# PowerTXBoard.net
KiCad netlist of a schematic drawn in EAGLE
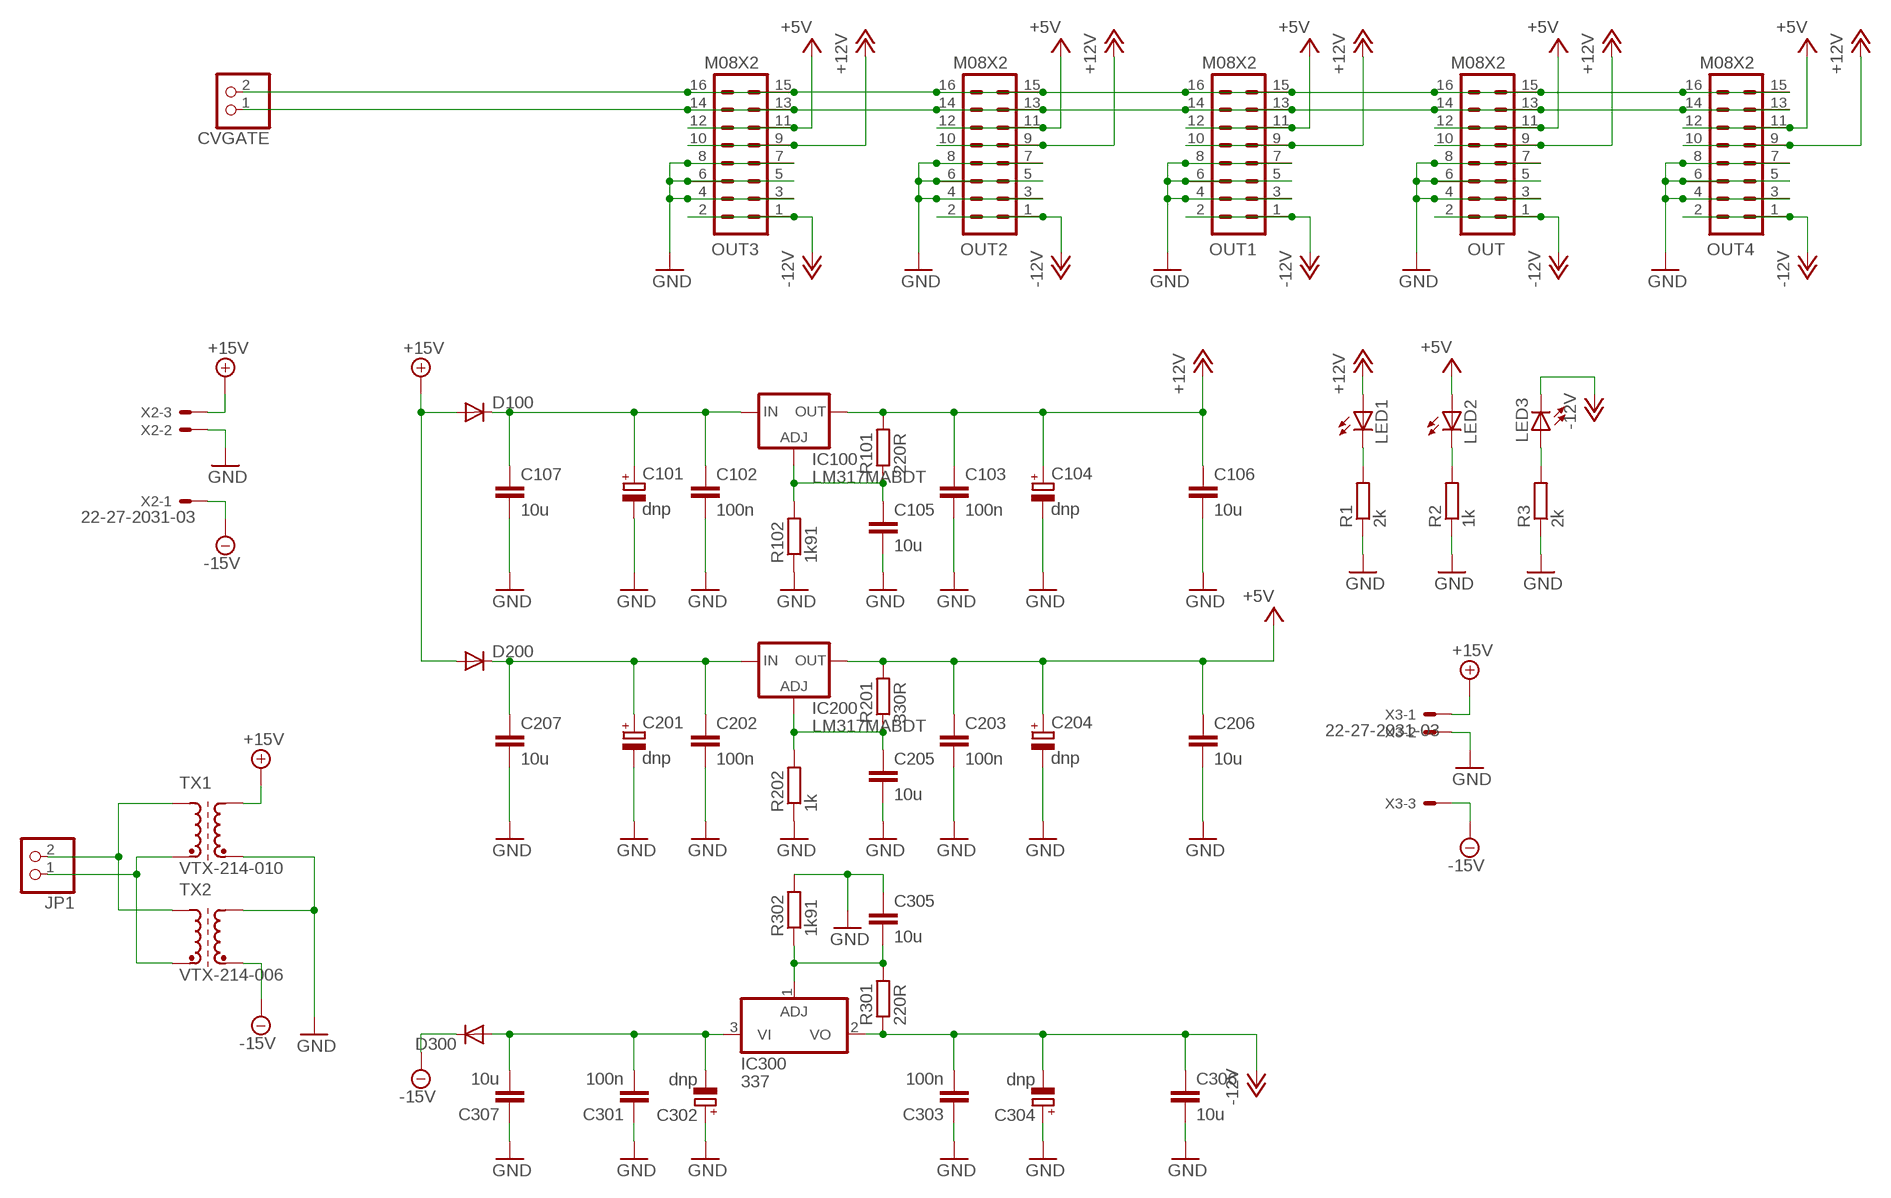
[diagram p0: schematic, sheet 1]

(export (version "E")
  (design (tool "Eeschema 10.0.6"))
  (components
    (comp (ref "C101")
      (value "dnp")
      (footprint "eagle-import:CPOL-5")
      (libsource (lib "eagle-import") (part "CPOL-EU153CLV-0505"))
    )
    (comp (ref "C102")
      (value "100n")
      (footprint "eagle-import:C0603")
      (libsource (lib "eagle-import") (part "C-EUC0603"))
    )
    (comp (ref "C103")
      (value "100n")
      (footprint "eagle-import:C0603")
      (libsource (lib "eagle-import") (part "C-EUC0603"))
    )
    (comp (ref "C104")
      (value "dnp")
      (footprint "eagle-import:CPOL-5")
      (libsource (lib "eagle-import") (part "CPOL-EU153CLV-0505"))
    )
    (comp (ref "C105")
      (value "10u")
      (footprint "eagle-import:C1206")
      (libsource (lib "eagle-import") (part "C-EUC1206"))
    )
    (comp (ref "C106")
      (value "10u")
      (footprint "eagle-import:C1206")
      (libsource (lib "eagle-import") (part "C-EUC1206"))
    )
    (comp (ref "C107")
      (value "10u")
      (footprint "eagle-import:C1206")
      (libsource (lib "eagle-import") (part "C-EUC1206"))
    )
    (comp (ref "C201")
      (value "dnp")
      (footprint "eagle-import:CPOL-5")
      (libsource (lib "eagle-import") (part "CPOL-EU153CLV-0505"))
    )
    (comp (ref "C202")
      (value "100n")
      (footprint "eagle-import:C0603")
      (libsource (lib "eagle-import") (part "C-EUC0603"))
    )
    (comp (ref "C203")
      (value "100n")
      (footprint "eagle-import:C0603")
      (libsource (lib "eagle-import") (part "C-EUC0603"))
    )
    (comp (ref "C204")
      (value "dnp")
      (footprint "eagle-import:CPOL-5")
      (libsource (lib "eagle-import") (part "CPOL-EU153CLV-0505"))
    )
    (comp (ref "C205")
      (value "10u")
      (footprint "eagle-import:C1206")
      (libsource (lib "eagle-import") (part "C-EUC1206"))
    )
    (comp (ref "C206")
      (value "10u")
      (footprint "eagle-import:C1206")
      (libsource (lib "eagle-import") (part "C-EUC1206"))
    )
    (comp (ref "C207")
      (value "10u")
      (footprint "eagle-import:C1206")
      (libsource (lib "eagle-import") (part "C-EUC1206"))
    )
    (comp (ref "C301")
      (value "100n")
      (footprint "eagle-import:C0603")
      (libsource (lib "eagle-import") (part "C-EUC0603"))
    )
    (comp (ref "C302")
      (value "dnp")
      (footprint "eagle-import:CPOL-5")
      (libsource (lib "eagle-import") (part "CPOL-EU153CLV-0505"))
    )
    (comp (ref "C303")
      (value "100n")
      (footprint "eagle-import:C0603")
      (libsource (lib "eagle-import") (part "C-EUC0603"))
    )
    (comp (ref "C304")
      (value "dnp")
      (footprint "eagle-import:CPOL-5")
      (libsource (lib "eagle-import") (part "CPOL-EU153CLV-0505"))
    )
    (comp (ref "C305")
      (value "10u")
      (footprint "eagle-import:C1206")
      (libsource (lib "eagle-import") (part "C-EUC1206"))
    )
    (comp (ref "C306")
      (value "10u")
      (footprint "eagle-import:C1206")
      (libsource (lib "eagle-import") (part "C-EUC1206"))
    )
    (comp (ref "C307")
      (value "10u")
      (footprint "eagle-import:C1206")
      (libsource (lib "eagle-import") (part "C-EUC1206"))
    )
    (comp (ref "CVGATE")
      (value "PINHD-1X2")
      (footprint "eagle-import:1X02")
      (libsource (lib "eagle-import") (part "PINHD-1X2"))
    )
    (comp (ref "D100")
      (value "DIODESMA")
      (footprint "eagle-import:SMA-DIODE")
      (libsource (lib "eagle-import") (part "DIODESMA"))
    )
    (comp (ref "D200")
      (value "DIODESMA")
      (footprint "eagle-import:SMA-DIODE")
      (libsource (lib "eagle-import") (part "DIODESMA"))
    )
    (comp (ref "D300")
      (value "DIODESMA")
      (footprint "eagle-import:SMA-DIODE")
      (libsource (lib "eagle-import") (part "DIODESMA"))
    )
    (comp (ref "IC100")
      (value "LM317MABDT")
      (footprint "eagle-import:DPACK")
      (libsource (lib "eagle-import") (part "v-reg_LM317?MABDT"))
    )
    (comp (ref "IC200")
      (value "LM317MABDT")
      (footprint "eagle-import:DPACK")
      (libsource (lib "eagle-import") (part "v-reg_LM317?MABDT"))
    )
    (comp (ref "IC300")
      (value "337")
      (footprint "eagle-import:TO252")
      (libsource (lib "eagle-import") (part "337"))
    )
    (comp (ref "JP1")
      (value "PINHD-1X2")
      (footprint "eagle-import:1X02")
      (libsource (lib "eagle-import") (part "PINHD-1X2"))
    )
    (comp (ref "LED1")
      (value "LEDCHIPLED_1206")
      (footprint "eagle-import:CHIPLED_1206")
      (libsource (lib "eagle-import") (part "LEDCHIPLED_1206"))
    )
    (comp (ref "LED2")
      (value "LEDCHIPLED_1206")
      (footprint "eagle-import:CHIPLED_1206")
      (libsource (lib "eagle-import") (part "LEDCHIPLED_1206"))
    )
    (comp (ref "LED3")
      (value "LEDCHIPLED_1206")
      (footprint "eagle-import:CHIPLED_1206")
      (libsource (lib "eagle-import") (part "LEDCHIPLED_1206"))
    )
    (comp (ref "OUT")
      (value "M08X2")
      (footprint "eagle-import:2X8")
      (libsource (lib "eagle-import") (part "M08X2"))
    )
    (comp (ref "OUT1")
      (value "M08X2")
      (footprint "eagle-import:2X8")
      (libsource (lib "eagle-import") (part "M08X2"))
    )
    (comp (ref "OUT2")
      (value "M08X2")
      (footprint "eagle-import:2X8")
      (libsource (lib "eagle-import") (part "M08X2"))
    )
    (comp (ref "OUT3")
      (value "M08X2")
      (footprint "eagle-import:2X8")
      (libsource (lib "eagle-import") (part "M08X2"))
    )
    (comp (ref "OUT4")
      (value "M08X2")
      (footprint "eagle-import:2X8")
      (libsource (lib "eagle-import") (part "M08X2"))
    )
    (comp (ref "R1")
      (value "2k")
      (footprint "eagle-import:0603")
      (libsource (lib "eagle-import") (part "R-EU_0603"))
    )
    (comp (ref "R2")
      (value "1k")
      (footprint "eagle-import:0603")
      (libsource (lib "eagle-import") (part "R-EU_0603"))
    )
    (comp (ref "R3")
      (value "2k")
      (footprint "eagle-import:0603")
      (libsource (lib "eagle-import") (part "R-EU_0603"))
    )
    (comp (ref "R101")
      (value "220R")
      (footprint "eagle-import:0603")
      (libsource (lib "eagle-import") (part "R-EU_0603"))
    )
    (comp (ref "R102")
      (value "1k91")
      (footprint "eagle-import:0603")
      (libsource (lib "eagle-import") (part "R-EU_0603"))
    )
    (comp (ref "R201")
      (value "330R")
      (footprint "eagle-import:0603")
      (libsource (lib "eagle-import") (part "R-EU_0603"))
    )
    (comp (ref "R202")
      (value "1k")
      (footprint "eagle-import:0603")
      (libsource (lib "eagle-import") (part "R-EU_0603"))
    )
    (comp (ref "R301")
      (value "220R")
      (footprint "eagle-import:0603")
      (libsource (lib "eagle-import") (part "R-EU_0603"))
    )
    (comp (ref "R302")
      (value "1k91")
      (footprint "eagle-import:0603")
      (libsource (lib "eagle-import") (part "R-EU_0603"))
    )
    (comp (ref "TX1")
      (value "VTX-214-010")
      (footprint "eagle-import:VTX-214-006")
      (libsource (lib "eagle-import") (part "VTX-214-006"))
    )
    (comp (ref "TX2")
      (value "VTX-214-006")
      (footprint "eagle-import:VTX-214-006")
      (libsource (lib "eagle-import") (part "VTX-214-006"))
    )
    (comp (ref "X2")
      (value "22-27-2031-03")
      (footprint "eagle-import:6410-03")
      (libsource (lib "eagle-import") (part "22-?-0327-2031"))
    )
    (comp (ref "X3")
      (value "22-27-2031-03")
      (footprint "eagle-import:6410-03")
      (libsource (lib "eagle-import") (part "22-?-0327-2031"))
    )
  )
  (nets
    (net (code "1") (name "+5V") (class "Default")
      (node (ref "C203") (pin "1") (pinfunction "1_1") (pintype "passive"))
      (node (ref "C204") (pin "+") (pinfunction "+_+") (pintype "passive"))
      (node (ref "C206") (pin "1") (pinfunction "1_1") (pintype "passive"))
      (node (ref "IC200") (pin "4") (pinfunction "OUT_4") (pintype "passive"))
      (node (ref "LED2") (pin "A") (pinfunction "A_A") (pintype "passive"))
      (node (ref "OUT") (pin "11") (pinfunction "11_11") (pintype "passive"))
      (node (ref "OUT") (pin "12") (pinfunction "12_12") (pintype "passive"))
      (node (ref "OUT1") (pin "11") (pinfunction "11_11") (pintype "passive"))
      (node (ref "OUT1") (pin "12") (pinfunction "12_12") (pintype "passive"))
      (node (ref "OUT2") (pin "11") (pinfunction "11_11") (pintype "passive"))
      (node (ref "OUT2") (pin "12") (pinfunction "12_12") (pintype "passive"))
      (node (ref "OUT3") (pin "11") (pinfunction "11_11") (pintype "passive"))
      (node (ref "OUT3") (pin "12") (pinfunction "12_12") (pintype "passive"))
      (node (ref "OUT4") (pin "11") (pinfunction "11_11") (pintype "passive"))
      (node (ref "OUT4") (pin "12") (pinfunction "12_12") (pintype "passive"))
      (node (ref "R201") (pin "2") (pinfunction "2_2") (pintype "passive"))
    )
    (net (code "2") (name "+12V") (class "Default")
      (node (ref "C103") (pin "1") (pinfunction "1_1") (pintype "passive"))
      (node (ref "C104") (pin "+") (pinfunction "+_+") (pintype "passive"))
      (node (ref "C106") (pin "1") (pinfunction "1_1") (pintype "passive"))
      (node (ref "IC100") (pin "4") (pinfunction "OUT_4") (pintype "passive"))
      (node (ref "LED1") (pin "A") (pinfunction "A_A") (pintype "passive"))
      (node (ref "OUT") (pin "10") (pinfunction "10_10") (pintype "passive"))
      (node (ref "OUT") (pin "9") (pinfunction "9_9") (pintype "passive"))
      (node (ref "OUT1") (pin "10") (pinfunction "10_10") (pintype "passive"))
      (node (ref "OUT1") (pin "9") (pinfunction "9_9") (pintype "passive"))
      (node (ref "OUT2") (pin "10") (pinfunction "10_10") (pintype "passive"))
      (node (ref "OUT2") (pin "9") (pinfunction "9_9") (pintype "passive"))
      (node (ref "OUT3") (pin "10") (pinfunction "10_10") (pintype "passive"))
      (node (ref "OUT3") (pin "9") (pinfunction "9_9") (pintype "passive"))
      (node (ref "OUT4") (pin "10") (pinfunction "10_10") (pintype "passive"))
      (node (ref "OUT4") (pin "9") (pinfunction "9_9") (pintype "passive"))
      (node (ref "R101") (pin "2") (pinfunction "2_2") (pintype "passive"))
    )
    (net (code "3") (name "+15V") (class "Default")
      (node (ref "D100") (pin "A") (pinfunction "A_A") (pintype "passive"))
      (node (ref "D200") (pin "A") (pinfunction "A_A") (pintype "passive"))
      (node (ref "TX1") (pin "P$3") (pinfunction "A2_P$3") (pintype "passive"))
      (node (ref "X2") (pin "3") (pinfunction "S_3") (pintype "passive"))
      (node (ref "X3") (pin "1") (pinfunction "S_1") (pintype "passive"))
    )
    (net (code "4") (name "-12V") (class "Default")
      (node (ref "C303") (pin "2") (pinfunction "2_2") (pintype "passive"))
      (node (ref "C304") (pin "-") (pinfunction "-_-") (pintype "passive"))
      (node (ref "C306") (pin "1") (pinfunction "1_1") (pintype "passive"))
      (node (ref "IC300") (pin "2") (pinfunction "VO_2") (pintype "passive"))
      (node (ref "LED3") (pin "C") (pinfunction "C_C") (pintype "passive"))
      (node (ref "OUT") (pin "1") (pinfunction "1_1") (pintype "passive"))
      (node (ref "OUT") (pin "2") (pinfunction "2_2") (pintype "passive"))
      (node (ref "OUT1") (pin "1") (pinfunction "1_1") (pintype "passive"))
      (node (ref "OUT1") (pin "2") (pinfunction "2_2") (pintype "passive"))
      (node (ref "OUT2") (pin "1") (pinfunction "1_1") (pintype "passive"))
      (node (ref "OUT2") (pin "2") (pinfunction "2_2") (pintype "passive"))
      (node (ref "OUT3") (pin "1") (pinfunction "1_1") (pintype "passive"))
      (node (ref "OUT3") (pin "2") (pinfunction "2_2") (pintype "passive"))
      (node (ref "OUT4") (pin "1") (pinfunction "1_1") (pintype "passive"))
      (node (ref "OUT4") (pin "2") (pinfunction "2_2") (pintype "passive"))
      (node (ref "R301") (pin "1") (pinfunction "1_1") (pintype "passive"))
    )
    (net (code "5") (name "-15V") (class "Default")
      (node (ref "D300") (pin "C") (pinfunction "C_C") (pintype "passive"))
      (node (ref "TX2") (pin "P$4") (pinfunction "E2_P$4") (pintype "passive"))
      (node (ref "X2") (pin "1") (pinfunction "S_1") (pintype "passive"))
      (node (ref "X3") (pin "3") (pinfunction "S_3") (pintype "passive"))
    )
    (net (code "6") (name "GND") (class "Default")
      (node (ref "C101") (pin "-") (pinfunction "-_-") (pintype "passive"))
      (node (ref "C102") (pin "2") (pinfunction "2_2") (pintype "passive"))
      (node (ref "C103") (pin "2") (pinfunction "2_2") (pintype "passive"))
      (node (ref "C104") (pin "-") (pinfunction "-_-") (pintype "passive"))
      (node (ref "C105") (pin "2") (pinfunction "2_2") (pintype "passive"))
      (node (ref "C106") (pin "2") (pinfunction "2_2") (pintype "passive"))
      (node (ref "C107") (pin "2") (pinfunction "2_2") (pintype "passive"))
      (node (ref "C201") (pin "-") (pinfunction "-_-") (pintype "passive"))
      (node (ref "C202") (pin "2") (pinfunction "2_2") (pintype "passive"))
      (node (ref "C203") (pin "2") (pinfunction "2_2") (pintype "passive"))
      (node (ref "C204") (pin "-") (pinfunction "-_-") (pintype "passive"))
      (node (ref "C205") (pin "2") (pinfunction "2_2") (pintype "passive"))
      (node (ref "C206") (pin "2") (pinfunction "2_2") (pintype "passive"))
      (node (ref "C207") (pin "2") (pinfunction "2_2") (pintype "passive"))
      (node (ref "C301") (pin "1") (pinfunction "1_1") (pintype "passive"))
      (node (ref "C302") (pin "+") (pinfunction "+_+") (pintype "passive"))
      (node (ref "C303") (pin "1") (pinfunction "1_1") (pintype "passive"))
      (node (ref "C304") (pin "+") (pinfunction "+_+") (pintype "passive"))
      (node (ref "C305") (pin "1") (pinfunction "1_1") (pintype "passive"))
      (node (ref "C306") (pin "2") (pinfunction "2_2") (pintype "passive"))
      (node (ref "C307") (pin "1") (pinfunction "1_1") (pintype "passive"))
      (node (ref "OUT") (pin "3") (pinfunction "3_3") (pintype "passive"))
      (node (ref "OUT") (pin "4") (pinfunction "4_4") (pintype "passive"))
      (node (ref "OUT") (pin "5") (pinfunction "5_5") (pintype "passive"))
      (node (ref "OUT") (pin "6") (pinfunction "6_6") (pintype "passive"))
      (node (ref "OUT") (pin "7") (pinfunction "7_7") (pintype "passive"))
      (node (ref "OUT") (pin "8") (pinfunction "8_8") (pintype "passive"))
      (node (ref "OUT1") (pin "3") (pinfunction "3_3") (pintype "passive"))
      (node (ref "OUT1") (pin "4") (pinfunction "4_4") (pintype "passive"))
      (node (ref "OUT1") (pin "5") (pinfunction "5_5") (pintype "passive"))
      (node (ref "OUT1") (pin "6") (pinfunction "6_6") (pintype "passive"))
      (node (ref "OUT1") (pin "7") (pinfunction "7_7") (pintype "passive"))
      (node (ref "OUT1") (pin "8") (pinfunction "8_8") (pintype "passive"))
      (node (ref "OUT2") (pin "3") (pinfunction "3_3") (pintype "passive"))
      (node (ref "OUT2") (pin "4") (pinfunction "4_4") (pintype "passive"))
      (node (ref "OUT2") (pin "5") (pinfunction "5_5") (pintype "passive"))
      (node (ref "OUT2") (pin "6") (pinfunction "6_6") (pintype "passive"))
      (node (ref "OUT2") (pin "7") (pinfunction "7_7") (pintype "passive"))
      (node (ref "OUT2") (pin "8") (pinfunction "8_8") (pintype "passive"))
      (node (ref "OUT3") (pin "3") (pinfunction "3_3") (pintype "passive"))
      (node (ref "OUT3") (pin "4") (pinfunction "4_4") (pintype "passive"))
      (node (ref "OUT3") (pin "5") (pinfunction "5_5") (pintype "passive"))
      (node (ref "OUT3") (pin "6") (pinfunction "6_6") (pintype "passive"))
      (node (ref "OUT3") (pin "7") (pinfunction "7_7") (pintype "passive"))
      (node (ref "OUT3") (pin "8") (pinfunction "8_8") (pintype "passive"))
      (node (ref "OUT4") (pin "3") (pinfunction "3_3") (pintype "passive"))
      (node (ref "OUT4") (pin "4") (pinfunction "4_4") (pintype "passive"))
      (node (ref "OUT4") (pin "5") (pinfunction "5_5") (pintype "passive"))
      (node (ref "OUT4") (pin "6") (pinfunction "6_6") (pintype "passive"))
      (node (ref "OUT4") (pin "7") (pinfunction "7_7") (pintype "passive"))
      (node (ref "OUT4") (pin "8") (pinfunction "8_8") (pintype "passive"))
      (node (ref "R1") (pin "1") (pinfunction "1_1") (pintype "passive"))
      (node (ref "R102") (pin "1") (pinfunction "1_1") (pintype "passive"))
      (node (ref "R2") (pin "1") (pinfunction "1_1") (pintype "passive"))
      (node (ref "R202") (pin "1") (pinfunction "1_1") (pintype "passive"))
      (node (ref "R3") (pin "1") (pinfunction "1_1") (pintype "passive"))
      (node (ref "R302") (pin "2") (pinfunction "2_2") (pintype "passive"))
      (node (ref "TX1") (pin "P$4") (pinfunction "E2_P$4") (pintype "passive"))
      (node (ref "TX2") (pin "P$3") (pinfunction "A2_P$3") (pintype "passive"))
      (node (ref "X2") (pin "2") (pinfunction "S_2") (pintype "passive"))
      (node (ref "X3") (pin "2") (pinfunction "S_2") (pintype "passive"))
    )
    (net (code "7") (name "Net-(CVGATE-Pad1)") (class "Default")
      (node (ref "CVGATE") (pin "1") (pinfunction "1_1") (pintype "passive"))
      (node (ref "OUT") (pin "13") (pinfunction "13_13") (pintype "passive"))
      (node (ref "OUT") (pin "14") (pinfunction "14_14") (pintype "passive"))
      (node (ref "OUT1") (pin "13") (pinfunction "13_13") (pintype "passive"))
      (node (ref "OUT1") (pin "14") (pinfunction "14_14") (pintype "passive"))
      (node (ref "OUT2") (pin "13") (pinfunction "13_13") (pintype "passive"))
      (node (ref "OUT2") (pin "14") (pinfunction "14_14") (pintype "passive"))
      (node (ref "OUT3") (pin "13") (pinfunction "13_13") (pintype "passive"))
      (node (ref "OUT3") (pin "14") (pinfunction "14_14") (pintype "passive"))
      (node (ref "OUT4") (pin "13") (pinfunction "13_13") (pintype "passive"))
      (node (ref "OUT4") (pin "14") (pinfunction "14_14") (pintype "passive"))
    )
    (net (code "8") (name "Net-(CVGATE-Pad2)") (class "Default")
      (node (ref "CVGATE") (pin "2") (pinfunction "2_2") (pintype "passive"))
      (node (ref "OUT") (pin "15") (pinfunction "15_15") (pintype "passive"))
      (node (ref "OUT") (pin "16") (pinfunction "16_16") (pintype "passive"))
      (node (ref "OUT1") (pin "15") (pinfunction "15_15") (pintype "passive"))
      (node (ref "OUT1") (pin "16") (pinfunction "16_16") (pintype "passive"))
      (node (ref "OUT2") (pin "15") (pinfunction "15_15") (pintype "passive"))
      (node (ref "OUT2") (pin "16") (pinfunction "16_16") (pintype "passive"))
      (node (ref "OUT3") (pin "15") (pinfunction "15_15") (pintype "passive"))
      (node (ref "OUT3") (pin "16") (pinfunction "16_16") (pintype "passive"))
      (node (ref "OUT4") (pin "15") (pinfunction "15_15") (pintype "passive"))
      (node (ref "OUT4") (pin "16") (pinfunction "16_16") (pintype "passive"))
    )
    (net (code "9") (name "Net-(IC100-ADJ)") (class "Default")
      (node (ref "C105") (pin "1") (pinfunction "1_1") (pintype "passive"))
      (node (ref "IC100") (pin "1") (pinfunction "ADJ_1") (pintype "input"))
      (node (ref "R101") (pin "1") (pinfunction "1_1") (pintype "passive"))
      (node (ref "R102") (pin "2") (pinfunction "2_2") (pintype "passive"))
    )
    (net (code "10") (name "Net-(IC100-IN)") (class "Default")
      (node (ref "C101") (pin "+") (pinfunction "+_+") (pintype "passive"))
      (node (ref "C102") (pin "1") (pinfunction "1_1") (pintype "passive"))
      (node (ref "C107") (pin "1") (pinfunction "1_1") (pintype "passive"))
      (node (ref "D100") (pin "C") (pinfunction "C_C") (pintype "passive"))
      (node (ref "IC100") (pin "3") (pinfunction "IN_3") (pintype "input"))
    )
    (net (code "11") (name "Net-(IC200-ADJ)") (class "Default")
      (node (ref "C205") (pin "1") (pinfunction "1_1") (pintype "passive"))
      (node (ref "IC200") (pin "1") (pinfunction "ADJ_1") (pintype "input"))
      (node (ref "R201") (pin "1") (pinfunction "1_1") (pintype "passive"))
      (node (ref "R202") (pin "2") (pinfunction "2_2") (pintype "passive"))
    )
    (net (code "12") (name "Net-(IC200-IN)") (class "Default")
      (node (ref "C201") (pin "+") (pinfunction "+_+") (pintype "passive"))
      (node (ref "C202") (pin "1") (pinfunction "1_1") (pintype "passive"))
      (node (ref "C207") (pin "1") (pinfunction "1_1") (pintype "passive"))
      (node (ref "D200") (pin "C") (pinfunction "C_C") (pintype "passive"))
      (node (ref "IC200") (pin "3") (pinfunction "IN_3") (pintype "input"))
    )
    (net (code "13") (name "Net-(IC300-ADJ)") (class "Default")
      (node (ref "C305") (pin "2") (pinfunction "2_2") (pintype "passive"))
      (node (ref "IC300") (pin "1") (pinfunction "ADJ_1") (pintype "input"))
      (node (ref "R301") (pin "2") (pinfunction "2_2") (pintype "passive"))
      (node (ref "R302") (pin "1") (pinfunction "1_1") (pintype "passive"))
    )
    (net (code "14") (name "Net-(IC300-VI)") (class "Default")
      (node (ref "C301") (pin "2") (pinfunction "2_2") (pintype "passive"))
      (node (ref "C302") (pin "-") (pinfunction "-_-") (pintype "passive"))
      (node (ref "C307") (pin "2") (pinfunction "2_2") (pintype "passive"))
      (node (ref "D300") (pin "A") (pinfunction "A_A") (pintype "passive"))
      (node (ref "IC300") (pin "3") (pinfunction "VI_3") (pintype "input"))
    )
    (net (code "15") (name "Net-(LED1-PadC)") (class "Default")
      (node (ref "LED1") (pin "C") (pinfunction "C_C") (pintype "passive"))
      (node (ref "R1") (pin "2") (pinfunction "2_2") (pintype "passive"))
    )
    (net (code "16") (name "Net-(LED2-PadC)") (class "Default")
      (node (ref "LED2") (pin "C") (pinfunction "C_C") (pintype "passive"))
      (node (ref "R2") (pin "2") (pinfunction "2_2") (pintype "passive"))
    )
    (net (code "17") (name "Net-(LED3-PadA)") (class "Default")
      (node (ref "LED3") (pin "A") (pinfunction "A_A") (pintype "passive"))
      (node (ref "R3") (pin "2") (pinfunction "2_2") (pintype "passive"))
    )
    (net (code "18") (name "Net-(TX1-A1)") (class "Default")
      (node (ref "JP1") (pin "2") (pinfunction "2_2") (pintype "passive"))
      (node (ref "TX1") (pin "P$1") (pinfunction "A1_P$1") (pintype "passive"))
      (node (ref "TX2") (pin "P$1") (pinfunction "A1_P$1") (pintype "passive"))
    )
    (net (code "19") (name "Net-(TX1-E1)") (class "Default")
      (node (ref "JP1") (pin "1") (pinfunction "1_1") (pintype "passive"))
      (node (ref "TX1") (pin "P$2") (pinfunction "E1_P$2") (pintype "passive"))
      (node (ref "TX2") (pin "P$2") (pinfunction "E1_P$2") (pintype "passive"))
    )
  )
)
